# LineOut.net
KiCad netlist of a schematic drawn in EAGLE
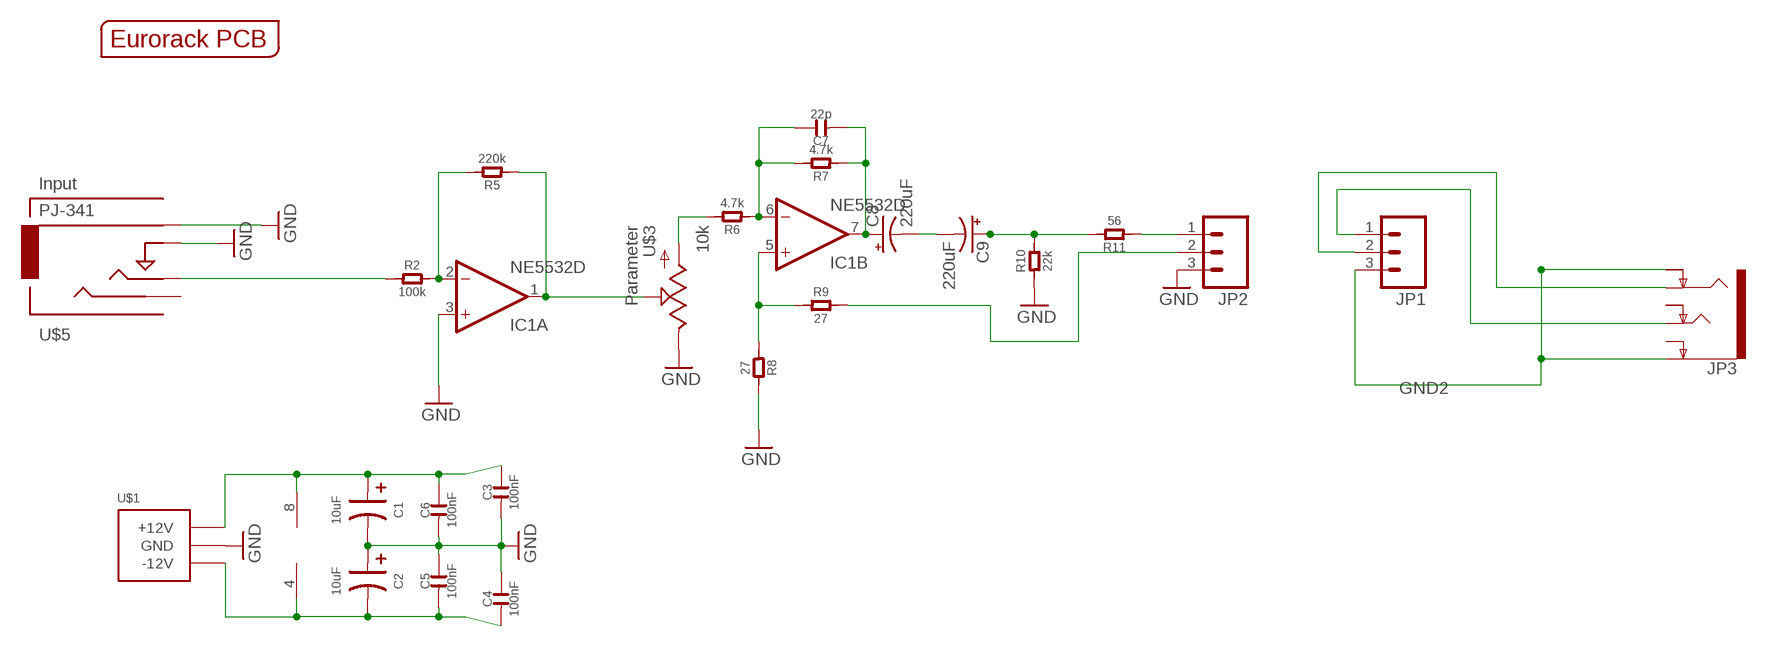
[diagram p0: schematic, sheet 1]

(export (version "E")
  (design (tool "Eeschema 10.0.6"))
  (components
    (comp (ref "C1")
      (value "10uF")
      (footprint "eagle-import:AVX-A")
      (libsource (lib "eagle-import") (part "C-POLAR-A"))
    )
    (comp (ref "C2")
      (value "10uF")
      (footprint "eagle-import:AVX-A")
      (libsource (lib "eagle-import") (part "C-POLAR-A"))
    )
    (comp (ref "C3")
      (value "100nF")
      (footprint "eagle-import:C0603")
      (libsource (lib "eagle-import") (part "C-0603"))
    )
    (comp (ref "C4")
      (value "100nF")
      (footprint "eagle-import:C0603")
      (libsource (lib "eagle-import") (part "C-0603"))
    )
    (comp (ref "C5")
      (value "100nF")
      (footprint "eagle-import:C0603")
      (libsource (lib "eagle-import") (part "C-0603"))
    )
    (comp (ref "C6")
      (value "100nF")
      (footprint "eagle-import:C0603")
      (libsource (lib "eagle-import") (part "C-0603"))
    )
    (comp (ref "C7")
      (value "22p")
      (footprint "eagle-import:C0603")
      (libsource (lib "eagle-import") (part "C-0603"))
    )
    (comp (ref "C8")
      (value "220uF")
      (footprint "eagle-import:153CLV-0505")
      (libsource (lib "eagle-import") (part "CPOL-US153CLV-0505"))
    )
    (comp (ref "C9")
      (value "220uF")
      (footprint "eagle-import:153CLV-0505")
      (libsource (lib "eagle-import") (part "CPOL-US153CLV-0505"))
    )
    (comp (ref "IC1")
      (value "NE5532D")
      (footprint "eagle-import:SO08")
      (libsource (lib "eagle-import") (part "NE5532D"))
    )
    (comp (ref "JP1")
      (value "M03PTH")
      (footprint "eagle-import:1X03")
      (libsource (lib "eagle-import") (part "M03PTH"))
    )
    (comp (ref "JP2")
      (value "M03PTH")
      (footprint "eagle-import:1X03")
      (libsource (lib "eagle-import") (part "M03PTH"))
    )
    (comp (ref "JP3")
      (value "AUDIO-JACK4-.25-HORIZ-TRS")
      (footprint "eagle-import:AUDIO-JACK-.25-INCH-HORIZ-PTH")
      (libsource (lib "eagle-import") (part "AUDIO-JACK4-.25-HORIZ-TRS"))
    )
    (comp (ref "R2")
      (value "100k")
      (footprint "eagle-import:R0603")
      (libsource (lib "eagle-import") (part "R-0603"))
    )
    (comp (ref "R5")
      (value "220k")
      (footprint "eagle-import:R0603")
      (libsource (lib "eagle-import") (part "R-0603"))
    )
    (comp (ref "R6")
      (value "4.7k")
      (footprint "eagle-import:R0603")
      (libsource (lib "eagle-import") (part "R-0603"))
    )
    (comp (ref "R7")
      (value "4.7k")
      (footprint "eagle-import:R0603")
      (libsource (lib "eagle-import") (part "R-0603"))
    )
    (comp (ref "R8")
      (value "27")
      (footprint "eagle-import:R0603")
      (libsource (lib "eagle-import") (part "R-0603"))
    )
    (comp (ref "R9")
      (value "27")
      (footprint "eagle-import:R0603")
      (libsource (lib "eagle-import") (part "R-0603"))
    )
    (comp (ref "R10")
      (value "22k")
      (footprint "eagle-import:R0603")
      (libsource (lib "eagle-import") (part "R-0603"))
    )
    (comp (ref "R11")
      (value "56")
      (footprint "eagle-import:R0603")
      (libsource (lib "eagle-import") (part "R-0603"))
    )
    (comp (ref "U$1")
      (value "POWER_SIMPLE10")
      (footprint "eagle-import:POWER_10")
      (libsource (lib "eagle-import") (part "POWER_SIMPLE10"))
    )
    (comp (ref "U$3")
      (value "10k")
      (footprint "eagle-import:OG-POTS_ALPS_POT_VERTICAL")
      (libsource (lib "eagle-import") (part "POTZEPHPOT"))
    )
    (comp (ref "U$5")
      (value "PJ-341")
      (footprint "eagle-import:3.5MM-JACK-SWITCH-13MM-INPUT")
      (libsource (lib "eagle-import") (part "AUDIO-JACKINPUT"))
    )
    (comp (ref "U$6")
      (value "EURORACK_PCB4HP")
      (footprint "eagle-import:EURORACK4HPPCB")
      (libsource (lib "eagle-import") (part "EURORACK_PCB4HP"))
    )
  )
  (nets
    (net (code "1") (name "/GND2") (class "Default")
      (node (ref "JP1") (pin "3") (pinfunction "3_3") (pintype "passive"))
      (node (ref "JP3") (pin "P$2") (pinfunction "EARTH_P$2") (pintype "bidirectional"))
      (node (ref "JP3") (pin "P$5") (pinfunction "RING-NORM_P$5") (pintype "bidirectional"))
    )
    (net (code "2") (name "GND") (class "Default")
      (node (ref "C1") (pin "-") (pinfunction "2_-") (pintype "bidirectional"))
      (node (ref "C2") (pin "+") (pinfunction "1_+") (pintype "bidirectional"))
      (node (ref "C3") (pin "1") (pinfunction "1_1") (pintype "bidirectional"))
      (node (ref "C4") (pin "2") (pinfunction "2_2") (pintype "bidirectional"))
      (node (ref "C5") (pin "2") (pinfunction "2_2") (pintype "bidirectional"))
      (node (ref "C6") (pin "1") (pinfunction "1_1") (pintype "bidirectional"))
      (node (ref "IC1") (pin "3") (pinfunction "+IN_3") (pintype "input"))
      (node (ref "JP2") (pin "3") (pinfunction "3_3") (pintype "passive"))
      (node (ref "R10") (pin "1") (pinfunction "1_1") (pintype "bidirectional"))
      (node (ref "R8") (pin "2") (pinfunction "2_2") (pintype "bidirectional"))
      (node (ref "U$1") (pin "3") (pinfunction "GND_3") (pintype "bidirectional"))
      (node (ref "U$1") (pin "4") (pinfunction "GND_4") (pintype "bidirectional"))
      (node (ref "U$1") (pin "5") (pinfunction "GND_5") (pintype "bidirectional"))
      (node (ref "U$1") (pin "6") (pinfunction "GND_6") (pintype "bidirectional"))
      (node (ref "U$1") (pin "7") (pinfunction "GND_7") (pintype "bidirectional"))
      (node (ref "U$1") (pin "8") (pinfunction "GND_8") (pintype "bidirectional"))
      (node (ref "U$3") (pin "P$1") (pinfunction "E_P$1") (pintype "passive"))
      (node (ref "U$5") (pin "RING@3") (pinfunction "RING_RING@3") (pintype "bidirectional"))
      (node (ref "U$5") (pin "SWITCH@3") (pinfunction "SWITCH_SWITCH@3") (pintype "bidirectional"))
    )
    (net (code "3") (name "Net-(C1-1)") (class "Default")
      (node (ref "C1") (pin "+") (pinfunction "1_+") (pintype "bidirectional"))
      (node (ref "C3") (pin "2") (pinfunction "2_2") (pintype "bidirectional"))
      (node (ref "C6") (pin "2") (pinfunction "2_2") (pintype "bidirectional"))
      (node (ref "IC1") (pin "8") (pinfunction "V+_8") (pintype "power_in"))
      (node (ref "U$1") (pin "10") (pinfunction "+12V_10") (pintype "bidirectional"))
      (node (ref "U$1") (pin "9") (pinfunction "+12V_9") (pintype "bidirectional"))
    )
    (net (code "4") (name "Net-(C2-2)") (class "Default")
      (node (ref "C2") (pin "-") (pinfunction "2_-") (pintype "bidirectional"))
      (node (ref "C4") (pin "1") (pinfunction "1_1") (pintype "bidirectional"))
      (node (ref "C5") (pin "1") (pinfunction "1_1") (pintype "bidirectional"))
      (node (ref "IC1") (pin "4") (pinfunction "V-_4") (pintype "power_in"))
      (node (ref "U$1") (pin "1") (pinfunction "-12V_1") (pintype "bidirectional"))
      (node (ref "U$1") (pin "2") (pinfunction "-12V_2") (pintype "bidirectional"))
    )
    (net (code "5") (name "Net-(C8-Pad-)") (class "Default")
      (node (ref "C8") (pin "-") (pinfunction "-_-") (pintype "passive"))
      (node (ref "C9") (pin "-") (pinfunction "-_-") (pintype "passive"))
    )
    (net (code "6") (name "Net-(C9-Pad+)") (class "Default")
      (node (ref "C9") (pin "+") (pinfunction "+_+") (pintype "passive"))
      (node (ref "R10") (pin "2") (pinfunction "2_2") (pintype "bidirectional"))
      (node (ref "R11") (pin "2") (pinfunction "2_2") (pintype "bidirectional"))
    )
    (net (code "7") (name "Net-(IC1A--IN)") (class "Default")
      (node (ref "IC1") (pin "2") (pinfunction "-IN_2") (pintype "input"))
      (node (ref "R2") (pin "2") (pinfunction "2_2") (pintype "bidirectional"))
      (node (ref "R5") (pin "2") (pinfunction "2_2") (pintype "bidirectional"))
    )
    (net (code "8") (name "Net-(IC1A-OUT)") (class "Default")
      (node (ref "IC1") (pin "1") (pinfunction "OUT_1") (pintype "output"))
      (node (ref "R5") (pin "1") (pinfunction "1_1") (pintype "bidirectional"))
      (node (ref "U$3") (pin "P$2") (pinfunction "S_P$2") (pintype "passive"))
    )
    (net (code "9") (name "Net-(IC1B-+IN)") (class "Default")
      (node (ref "IC1") (pin "5") (pinfunction "+IN_5") (pintype "input"))
      (node (ref "R8") (pin "1") (pinfunction "1_1") (pintype "bidirectional"))
      (node (ref "R9") (pin "1") (pinfunction "1_1") (pintype "bidirectional"))
    )
    (net (code "10") (name "Net-(IC1B--IN)") (class "Default")
      (node (ref "C7") (pin "2") (pinfunction "2_2") (pintype "bidirectional"))
      (node (ref "IC1") (pin "6") (pinfunction "-IN_6") (pintype "input"))
      (node (ref "R6") (pin "1") (pinfunction "1_1") (pintype "bidirectional"))
      (node (ref "R7") (pin "2") (pinfunction "2_2") (pintype "bidirectional"))
    )
    (net (code "11") (name "Net-(IC1B-OUT)") (class "Default")
      (node (ref "C7") (pin "1") (pinfunction "1_1") (pintype "bidirectional"))
      (node (ref "C8") (pin "+") (pinfunction "+_+") (pintype "passive"))
      (node (ref "IC1") (pin "7") (pinfunction "OUT_7") (pintype "output"))
      (node (ref "R7") (pin "1") (pinfunction "1_1") (pintype "bidirectional"))
    )
    (net (code "12") (name "Net-(JP2-Pad1)") (class "Default")
      (node (ref "JP2") (pin "1") (pinfunction "1_1") (pintype "passive"))
      (node (ref "R11") (pin "1") (pinfunction "1_1") (pintype "bidirectional"))
    )
    (net (code "13") (name "Net-(JP2-Pad2)") (class "Default")
      (node (ref "JP2") (pin "2") (pinfunction "2_2") (pintype "passive"))
      (node (ref "R9") (pin "2") (pinfunction "2_2") (pintype "bidirectional"))
    )
    (net (code "14") (name "Net-(JP3-RING)") (class "Default")
      (node (ref "JP1") (pin "2") (pinfunction "2_2") (pintype "passive"))
      (node (ref "JP3") (pin "P$4") (pinfunction "RING_P$4") (pintype "bidirectional"))
    )
    (net (code "15") (name "Net-(JP3-TIP)") (class "Default")
      (node (ref "JP1") (pin "1") (pinfunction "1_1") (pintype "passive"))
      (node (ref "JP3") (pin "P$6") (pinfunction "TIP_P$6") (pintype "bidirectional"))
    )
    (net (code "16") (name "Net-(U$3-A)") (class "Default")
      (node (ref "R6") (pin "2") (pinfunction "2_2") (pintype "bidirectional"))
      (node (ref "U$3") (pin "P$3") (pinfunction "A_P$3") (pintype "passive"))
    )
    (net (code "17") (name "Net-(U$5-TIP)") (class "Default")
      (node (ref "R2") (pin "1") (pinfunction "1_1") (pintype "bidirectional"))
      (node (ref "U$5") (pin "TIP@3") (pinfunction "TIP_TIP@3") (pintype "bidirectional"))
    )
    (net (code "18") (name "unconnected-(JP3-EARTH-NORM-PadP$3)") (class "Default")
      (node (ref "JP3") (pin "P$3") (pinfunction "EARTH-NORM_P$3") (pintype "bidirectional"))
    )
    (net (code "19") (name "unconnected-(JP3-TIP-NORM-PadP$7)") (class "Default")
      (node (ref "JP3") (pin "P$7") (pinfunction "TIP-NORM_P$7") (pintype "bidirectional"))
    )
    (net (code "20") (name "unconnected-(U$5-SECOND-PadSECOND@3)") (class "Default")
      (node (ref "U$5") (pin "SECOND@3") (pinfunction "SECOND_SECOND@3") (pintype "bidirectional"))
    )
  )
)
